# SCH_Genie-V1_2024-08-01.net
KiCad netlist of a schematic drawn in EasyEDA
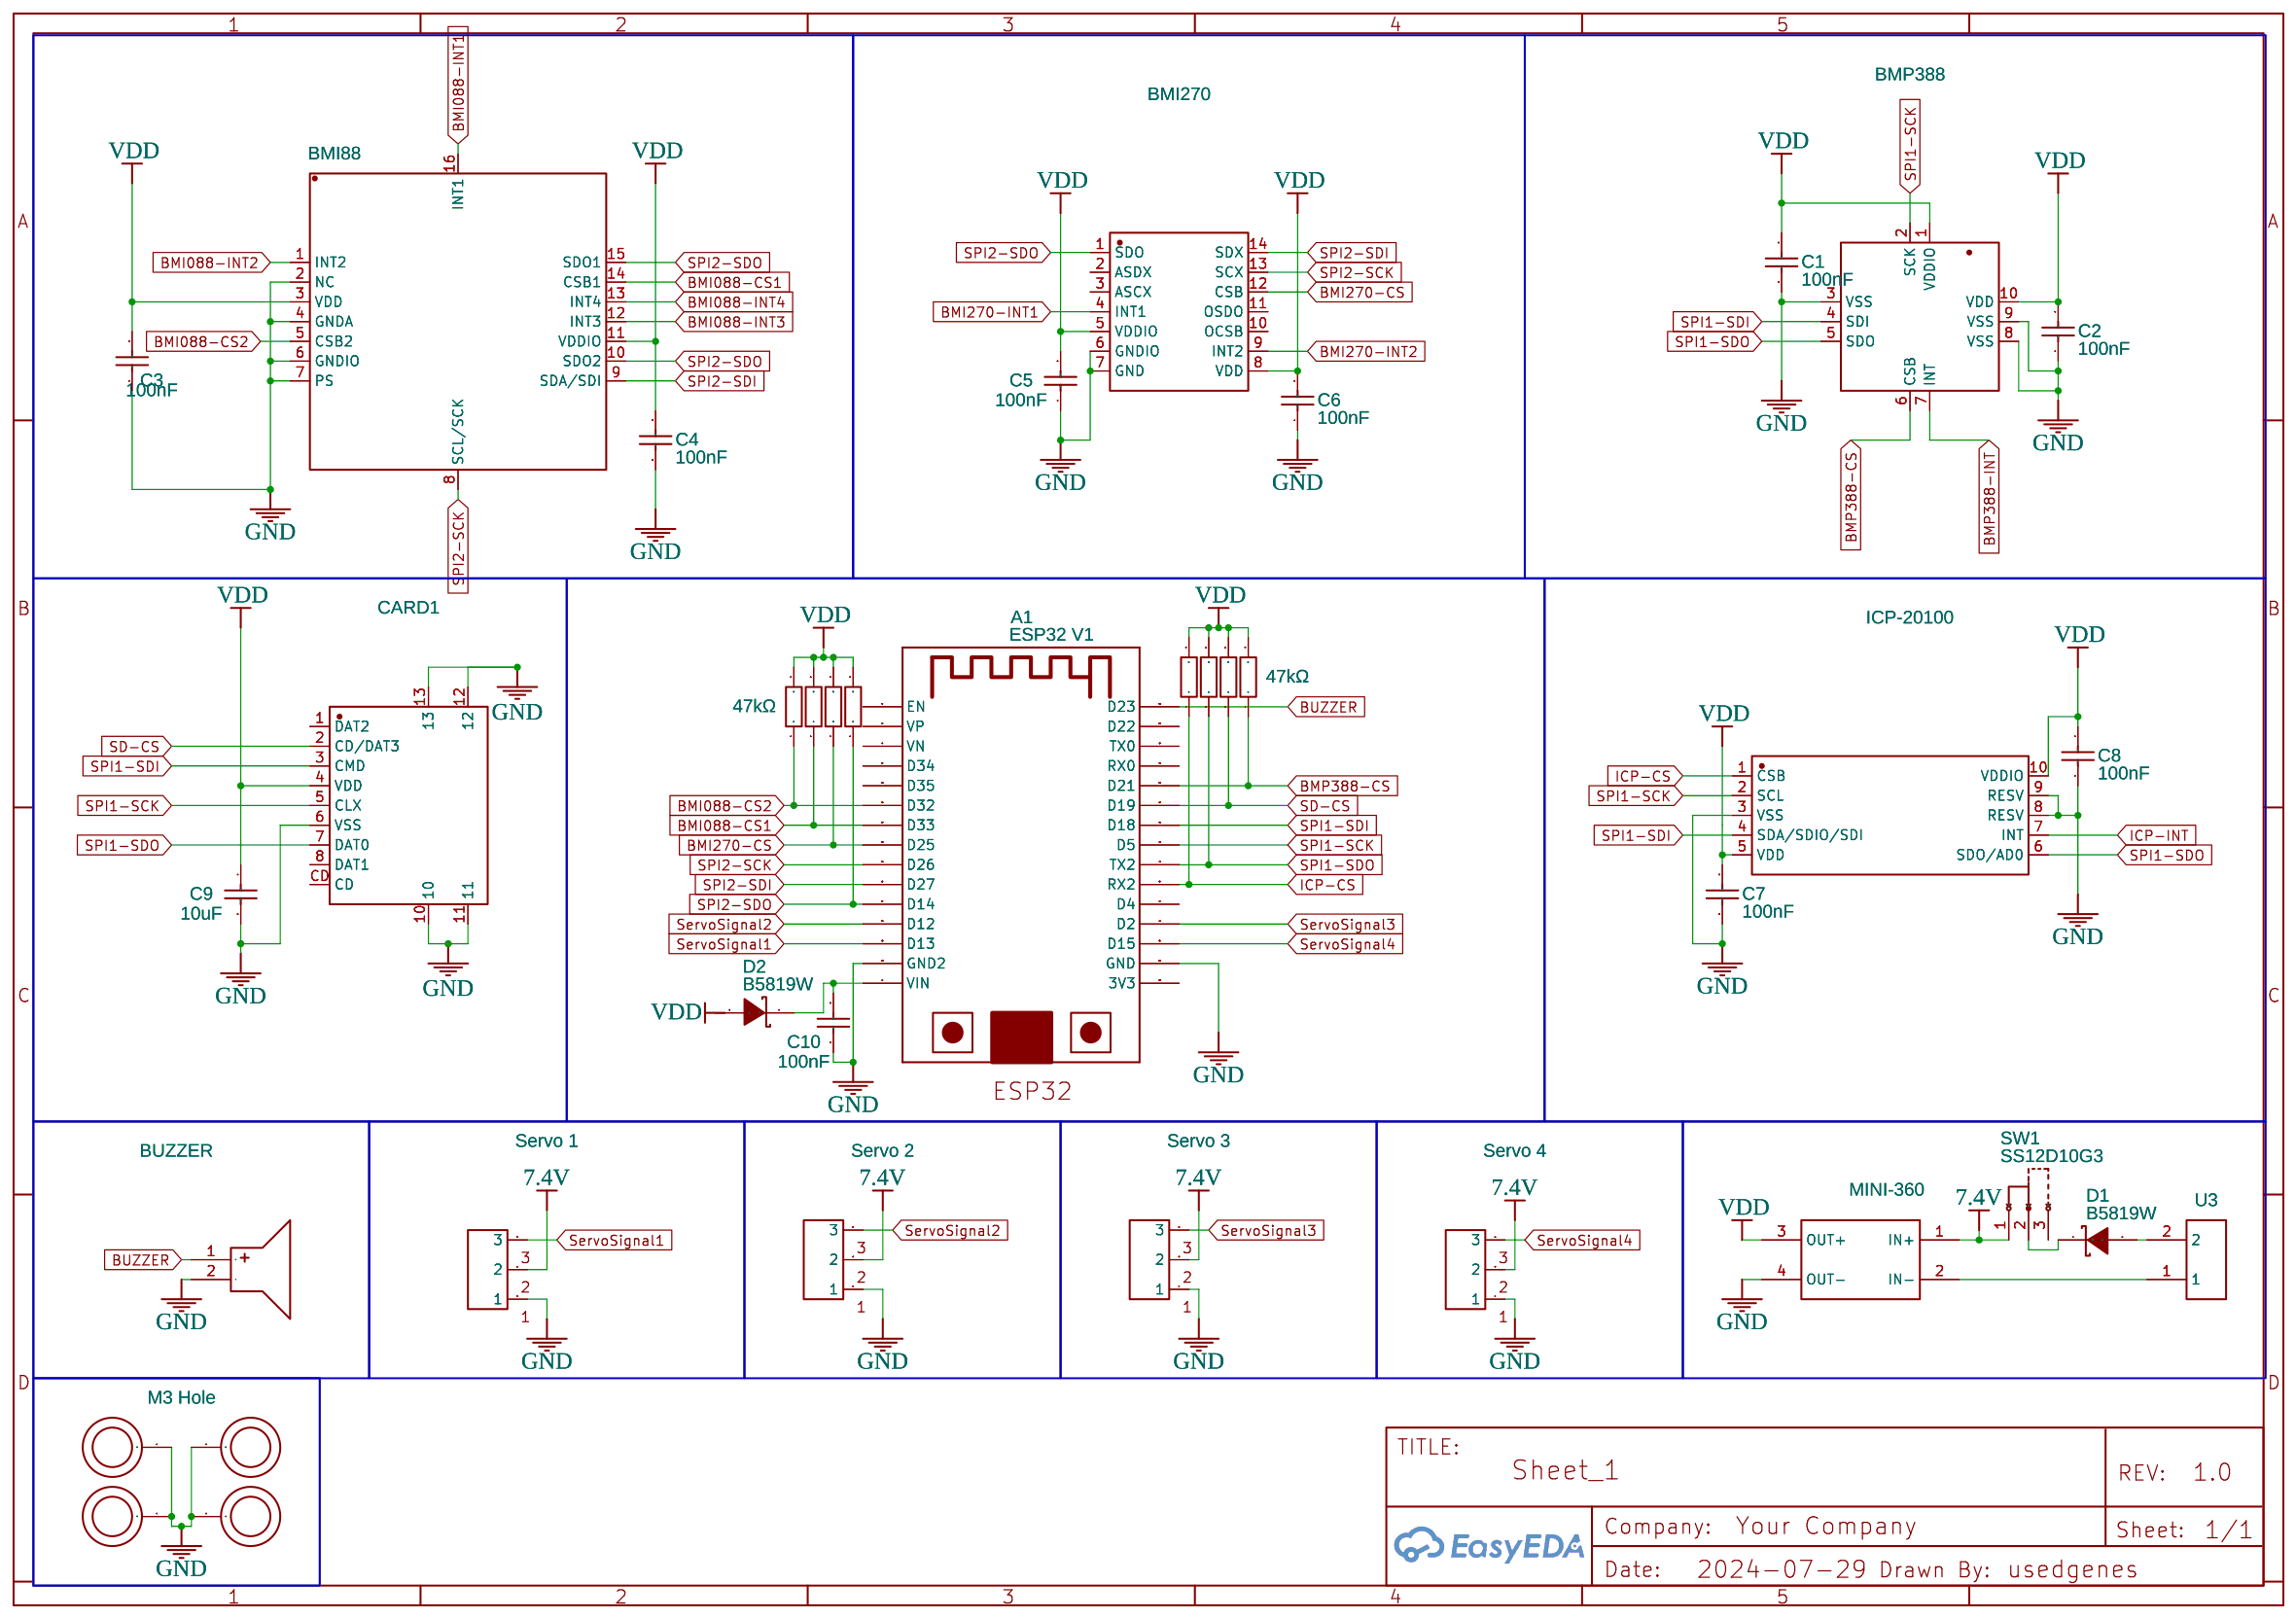
[diagram p0: schematic sheet]

(export (version "E")
  (design (tool "Eeschema 10.0.6"))
  (components
    (comp (ref "A1") (value "ESP32 V1") (libsource (lib "") (part "ESP32-DEVKIT-V1-30PIN")))
    (comp (ref "BMI88")
      (value "BMI088")
      (fields (field (name "Manufacturer") "Bosch(博世)"))
      (libsource (lib "") (part "BMI088"))
    )
    (comp (ref "BMI270")
      (value "BMI270")
      (fields (field (name "Manufacturer") "Bosch(博世)"))
      (libsource (lib "") (part "BMI270"))
    )
    (comp (ref "BMP388")
      (value "BMP388")
      (fields (field (name "Manufacturer") "Bosch(博世)"))
      (libsource (lib "") (part "BMP388"))
    )
    (comp (ref "BUZZER")
      (value "4000Hz")
      (fields
        (field (name "Manufacturer Part") "SKY-1475-0540-45P7.6")
        (field (name "Manufacturer") "S&S(海旭)")
      )
      (libsource (lib "") (part "SKY-1475-0540-45P7.6"))
    )
    (comp (ref "C1")
      (value "100nF")
      (fields
        (field (name "Manufacturer Part") "CL05B104KO5NNNC")
        (field (name "Manufacturer") "SAMSUNG(三星)")
      )
      (libsource (lib "") (part "CL05B104KO5NNNC"))
    )
    (comp (ref "C2")
      (value "100nF")
      (fields
        (field (name "Manufacturer Part") "CL05B104KO5NNNC")
        (field (name "Manufacturer") "SAMSUNG(三星)")
      )
      (libsource (lib "") (part "CL05B104KO5NNNC"))
    )
    (comp (ref "C3")
      (value "100nF")
      (fields
        (field (name "Manufacturer Part") "CL05B104KO5NNNC")
        (field (name "Manufacturer") "SAMSUNG(三星)")
      )
      (libsource (lib "") (part "CL05B104KO5NNNC"))
    )
    (comp (ref "C4")
      (value "100nF")
      (fields
        (field (name "Manufacturer Part") "CL05B104KO5NNNC")
        (field (name "Manufacturer") "SAMSUNG(三星)")
      )
      (libsource (lib "") (part "CL05B104KO5NNNC"))
    )
    (comp (ref "C5")
      (value "100nF")
      (fields
        (field (name "Manufacturer Part") "CL05B104KO5NNNC")
        (field (name "Manufacturer") "SAMSUNG(三星)")
      )
      (libsource (lib "") (part "CL05B104KO5NNNC"))
    )
    (comp (ref "C6")
      (value "100nF")
      (fields
        (field (name "Manufacturer Part") "CL05B104KO5NNNC")
        (field (name "Manufacturer") "SAMSUNG(三星)")
      )
      (libsource (lib "") (part "CL05B104KO5NNNC"))
    )
    (comp (ref "C7")
      (value "100nF")
      (fields
        (field (name "Manufacturer Part") "CL05B104KO5NNNC")
        (field (name "Manufacturer") "SAMSUNG(三星)")
      )
      (libsource (lib "") (part "CL05B104KO5NNNC"))
    )
    (comp (ref "C8")
      (value "100nF")
      (fields
        (field (name "Manufacturer Part") "CL05B104KO5NNNC")
        (field (name "Manufacturer") "SAMSUNG(三星)")
      )
      (libsource (lib "") (part "CL05B104KO5NNNC"))
    )
    (comp (ref "C9")
      (value "10uF")
      (fields
        (field (name "Manufacturer Part") "CL05A106MQ5NUNC")
        (field (name "Manufacturer") "SAMSUNG(三星)")
      )
      (libsource (lib "") (part "CL05A106MQ5NUNC"))
    )
    (comp (ref "C10")
      (value "100nF")
      (fields
        (field (name "Manufacturer Part") "CL05B104KO5NNNC")
        (field (name "Manufacturer") "SAMSUNG(三星)")
      )
      (libsource (lib "") (part "CL05B104KO5NNNC"))
    )
    (comp (ref "CARD1")
      (value "TF PUSH")
      (fields (field (name "Manufacturer") "SHOU HAN(首韩)"))
      (libsource (lib "") (part "TF PUSH"))
    )
    (comp (ref "D1")
      (value "B5819W")
      (fields (field (name "Manufacturer") "MDD(辰达半导体)"))
      (libsource (lib "") (part "B5819W_1"))
    )
    (comp (ref "D2")
      (value "B5819W")
      (fields (field (name "Manufacturer") "MDD(辰达半导体)"))
      (libsource (lib "") (part "B5819W"))
    )
    (comp (ref "H1") (value "M3 Hole") (libsource (lib "") (part "3MM_HOLE_1")))
    (comp (ref "H2") (value "3MM_HOLE") (libsource (lib "") (part "3MM_HOLE")))
    (comp (ref "H3") (value "3MM_HOLE") (libsource (lib "") (part "3MM_HOLE_1")))
    (comp (ref "H4") (value "3MM_HOLE") (libsource (lib "") (part "3MM_HOLE")))
    (comp (ref "ICP-20100")
      (value "ICP-20100")
      (fields (field (name "Manufacturer") "TDK"))
      (libsource (lib "") (part "ICP-20100"))
    )
    (comp (ref "MINI-360") (value "MINI-360") (libsource (lib "") (part "MINI-360")))
    (comp (ref "P1")
      (value "Servo 1")
      (fields
        (field (name "Manufacturer Part") "Female headerHDR1X8-2.54")
        (field (name "Manufacturer") "BOOMELE")
      )
      (libsource (lib "") (part "HEADER PAD 3X RMM COPY"))
    )
    (comp (ref "P2")
      (value "Servo 2")
      (fields
        (field (name "Manufacturer Part") "Female headerHDR1X8-2.54")
        (field (name "Manufacturer") "BOOMELE")
      )
      (libsource (lib "") (part "HEADER PAD 3X RMM COPY"))
    )
    (comp (ref "P3")
      (value "Servo 3")
      (fields
        (field (name "Manufacturer Part") "Female headerHDR1X8-2.54")
        (field (name "Manufacturer") "BOOMELE")
      )
      (libsource (lib "") (part "HEADER PAD 3X RMM COPY"))
    )
    (comp (ref "P4")
      (value "Servo 4")
      (fields
        (field (name "Manufacturer Part") "Female headerHDR1X8-2.54")
        (field (name "Manufacturer") "BOOMELE")
      )
      (libsource (lib "") (part "HEADER PAD 3X RMM COPY"))
    )
    (comp (ref "R1")
      (value "47kΩ")
      (fields
        (field (name "Manufacturer Part") "0402WGF4702TCE")
        (field (name "Manufacturer") "UNI-ROYAL(厚声)")
      )
      (libsource (lib "") (part "0402WGF4702TCE"))
    )
    (comp (ref "R2")
      (value "47kΩ")
      (fields
        (field (name "Manufacturer Part") "0402WGF4702TCE")
        (field (name "Manufacturer") "UNI-ROYAL(厚声)")
      )
      (libsource (lib "") (part "0402WGF4702TCE"))
    )
    (comp (ref "R3")
      (value "47kΩ")
      (fields
        (field (name "Manufacturer Part") "0402WGF4702TCE")
        (field (name "Manufacturer") "UNI-ROYAL(厚声)")
      )
      (libsource (lib "") (part "0402WGF4702TCE"))
    )
    (comp (ref "R4")
      (value "47kΩ")
      (fields
        (field (name "Manufacturer Part") "0402WGF4702TCE")
        (field (name "Manufacturer") "UNI-ROYAL(厚声)")
      )
      (libsource (lib "") (part "0402WGF4702TCE"))
    )
    (comp (ref "R5")
      (value "47kΩ")
      (fields
        (field (name "Manufacturer Part") "0402WGF4702TCE")
        (field (name "Manufacturer") "UNI-ROYAL(厚声)")
      )
      (libsource (lib "") (part "0402WGF4702TCE"))
    )
    (comp (ref "R7")
      (value "47kΩ")
      (fields
        (field (name "Manufacturer Part") "0402WGF4702TCE")
        (field (name "Manufacturer") "UNI-ROYAL(厚声)")
      )
      (libsource (lib "") (part "0402WGF4702TCE"))
    )
    (comp (ref "R8")
      (value "47kΩ")
      (fields
        (field (name "Manufacturer Part") "0402WGF4702TCE")
        (field (name "Manufacturer") "UNI-ROYAL(厚声)")
      )
      (libsource (lib "") (part "0402WGF4702TCE"))
    )
    (comp (ref "R9")
      (value "47kΩ")
      (fields
        (field (name "Manufacturer Part") "0402WGF4702TCE")
        (field (name "Manufacturer") "UNI-ROYAL(厚声)")
      )
      (libsource (lib "") (part "0402WGF4702TCE"))
    )
    (comp (ref "SW1")
      (value "SS12D10G3")
      (fields (field (name "Manufacturer") "SHOU HAN(首韩)"))
      (libsource (lib "") (part "SS12D10G3"))
    )
    (comp (ref "U3") (value "Power Pins") (libsource (lib "") (part "1X2")))
  )
  (nets
    (net (code "1") (name "7.4V") (class "Default")
      (node (ref "MINI-360") (pin "1") (pinfunction "IN+_1") (pintype "unspecified"))
      (node (ref "P1") (pin "2") (pinfunction "2_2") (pintype "unspecified"))
      (node (ref "P2") (pin "2") (pinfunction "2_2") (pintype "unspecified"))
      (node (ref "P3") (pin "2") (pinfunction "2_2") (pintype "unspecified"))
      (node (ref "P4") (pin "2") (pinfunction "2_2") (pintype "unspecified"))
      (node (ref "SW1") (pin "1") (pinfunction "1_1") (pintype "unspecified"))
    )
    (net (code "2") (name "BMI088-CS1") (class "Default")
      (node (ref "A1") (pin "D33") (pinfunction "D33_D33") (pintype "unspecified"))
      (node (ref "BMI88") (pin "14") (pinfunction "CSB1_14") (pintype "unspecified"))
      (node (ref "R1") (pin "1") (pinfunction "1_1") (pintype "input"))
    )
    (net (code "3") (name "BMI088-CS2") (class "Default")
      (node (ref "A1") (pin "D32") (pinfunction "D32_D32") (pintype "unspecified"))
      (node (ref "BMI88") (pin "5") (pinfunction "CSB2_5") (pintype "unspecified"))
      (node (ref "R4") (pin "1") (pinfunction "1_1") (pintype "input"))
    )
    (net (code "4") (name "BMI088-INT1") (class "Default")
      (node (ref "BMI88") (pin "16") (pinfunction "INT1_16") (pintype "unspecified"))
    )
    (net (code "5") (name "BMI088-INT2") (class "Default")
      (node (ref "BMI88") (pin "1") (pinfunction "INT2_1") (pintype "unspecified"))
    )
    (net (code "6") (name "BMI088-INT3") (class "Default")
      (node (ref "BMI88") (pin "12") (pinfunction "INT3_12") (pintype "unspecified"))
    )
    (net (code "7") (name "BMI088-INT4") (class "Default")
      (node (ref "BMI88") (pin "13") (pinfunction "INT4_13") (pintype "unspecified"))
    )
    (net (code "8") (name "BMI270-CS") (class "Default")
      (node (ref "A1") (pin "D25") (pinfunction "D25_D25") (pintype "unspecified"))
      (node (ref "BMI270") (pin "12") (pinfunction "CSB_12") (pintype "unspecified"))
      (node (ref "R2") (pin "1") (pinfunction "1_1") (pintype "input"))
    )
    (net (code "9") (name "BMI270-INT1") (class "Default")
      (node (ref "BMI270") (pin "4") (pinfunction "INT1_4") (pintype "unspecified"))
    )
    (net (code "10") (name "BMI270-INT2") (class "Default")
      (node (ref "BMI270") (pin "9") (pinfunction "INT2_9") (pintype "unspecified"))
    )
    (net (code "11") (name "BMP388-CS") (class "Default")
      (node (ref "A1") (pin "D21") (pinfunction "D21_D21") (pintype "unspecified"))
      (node (ref "BMP388") (pin "6") (pinfunction "CSB_6") (pintype "unspecified"))
      (node (ref "R5") (pin "1") (pinfunction "1_1") (pintype "input"))
    )
    (net (code "12") (name "BMP388-INT") (class "Default")
      (node (ref "BMP388") (pin "7") (pinfunction "INT_7") (pintype "unspecified"))
    )
    (net (code "13") (name "BUZZER") (class "Default")
      (node (ref "A1") (pin "D23") (pinfunction "D23_D23") (pintype "unspecified"))
      (node (ref "BUZZER") (pin "1") (pinfunction "+_1") (pintype "unspecified"))
    )
    (net (code "14") (name "GND") (class "Default")
      (node (ref "A1") (pin "GND") (pinfunction "GND_GND") (pintype "unspecified"))
      (node (ref "A1") (pin "GND2") (pinfunction "GND2_GND2") (pintype "unspecified"))
      (node (ref "BMI270") (pin "6") (pinfunction "GNDIO_6") (pintype "unspecified"))
      (node (ref "BMI270") (pin "7") (pinfunction "GND_7") (pintype "unspecified"))
      (node (ref "BMI88") (pin "2") (pinfunction "NC_2") (pintype "unspecified"))
      (node (ref "BMI88") (pin "4") (pinfunction "GNDA_4") (pintype "unspecified"))
      (node (ref "BMI88") (pin "6") (pinfunction "GNDIO_6") (pintype "unspecified"))
      (node (ref "BMI88") (pin "7") (pinfunction "PS_7") (pintype "unspecified"))
      (node (ref "BMP388") (pin "3") (pinfunction "VSS_3") (pintype "unspecified"))
      (node (ref "BMP388") (pin "8") (pinfunction "VSS_8") (pintype "unspecified"))
      (node (ref "BMP388") (pin "9") (pinfunction "VSS_9") (pintype "unspecified"))
      (node (ref "BUZZER") (pin "2") (pinfunction "-_2") (pintype "unspecified"))
      (node (ref "C1") (pin "1") (pinfunction "1_1") (pintype "input"))
      (node (ref "C10") (pin "1") (pinfunction "1_1") (pintype "input"))
      (node (ref "C2") (pin "1") (pinfunction "1_1") (pintype "input"))
      (node (ref "C3") (pin "1") (pinfunction "1_1") (pintype "input"))
      (node (ref "C4") (pin "1") (pinfunction "1_1") (pintype "input"))
      (node (ref "C5") (pin "1") (pinfunction "1_1") (pintype "input"))
      (node (ref "C6") (pin "1") (pinfunction "1_1") (pintype "input"))
      (node (ref "C7") (pin "1") (pinfunction "1_1") (pintype "input"))
      (node (ref "C8") (pin "1") (pinfunction "1_1") (pintype "input"))
      (node (ref "C9") (pin "2") (pinfunction "2_2") (pintype "input"))
      (node (ref "CARD1") (pin "10") (pinfunction "10_10") (pintype "unspecified"))
      (node (ref "CARD1") (pin "11") (pinfunction "11_11") (pintype "unspecified"))
      (node (ref "CARD1") (pin "12") (pinfunction "12_12") (pintype "unspecified"))
      (node (ref "CARD1") (pin "13") (pinfunction "13_13") (pintype "unspecified"))
      (node (ref "CARD1") (pin "6") (pinfunction "VSS_6") (pintype "unspecified"))
      (node (ref "H1") (pin "1") (pinfunction "1_1") (pintype "bidirectional"))
      (node (ref "H2") (pin "1") (pinfunction "1_1") (pintype "bidirectional"))
      (node (ref "H3") (pin "1") (pinfunction "1_1") (pintype "bidirectional"))
      (node (ref "H4") (pin "1") (pinfunction "1_1") (pintype "bidirectional"))
      (node (ref "ICP-20100") (pin "3") (pinfunction "VSS_3") (pintype "unspecified"))
      (node (ref "ICP-20100") (pin "8") (pinfunction "RESV_8") (pintype "unspecified"))
      (node (ref "ICP-20100") (pin "9") (pinfunction "RESV_9") (pintype "unspecified"))
      (node (ref "MINI-360") (pin "4") (pinfunction "OUT-_4") (pintype "unspecified"))
      (node (ref "P1") (pin "1") (pinfunction "1_1") (pintype "unspecified"))
      (node (ref "P2") (pin "1") (pinfunction "1_1") (pintype "unspecified"))
      (node (ref "P3") (pin "1") (pinfunction "1_1") (pintype "unspecified"))
      (node (ref "P4") (pin "1") (pinfunction "1_1") (pintype "unspecified"))
    )
    (net (code "15") (name "ICP-CS") (class "Default")
      (node (ref "A1") (pin "RX2") (pinfunction "RX2_RX2") (pintype "unspecified"))
      (node (ref "ICP-20100") (pin "1") (pinfunction "CSB_1") (pintype "unspecified"))
      (node (ref "R8") (pin "1") (pinfunction "1_1") (pintype "input"))
    )
    (net (code "16") (name "ICP-INT") (class "Default")
      (node (ref "ICP-20100") (pin "7") (pinfunction "INT_7") (pintype "unspecified"))
    )
    (net (code "17") (name "Net-(D1-A)") (class "Default")
      (node (ref "D1") (pin "2") (pinfunction "A_2") (pintype "unspecified"))
      (node (ref "U3") (pin "2") (pinfunction "2_2") (pintype "unspecified"))
    )
    (net (code "18") (name "Net-(D1-K)") (class "Default")
      (node (ref "D1") (pin "1") (pinfunction "K_1") (pintype "unspecified"))
      (node (ref "SW1") (pin "2") (pinfunction "2_2") (pintype "unspecified"))
    )
    (net (code "19") (name "Net-(D2-K)") (class "Default")
      (node (ref "A1") (pin "VIN") (pinfunction "VIN_VIN") (pintype "unspecified"))
      (node (ref "C10") (pin "2") (pinfunction "2_2") (pintype "input"))
      (node (ref "D2") (pin "1") (pinfunction "K_1") (pintype "unspecified"))
    )
    (net (code "20") (name "Net-(MINI-360-IN-)") (class "Default")
      (node (ref "MINI-360") (pin "2") (pinfunction "IN-_2") (pintype "unspecified"))
      (node (ref "U3") (pin "1") (pinfunction "1_1") (pintype "unspecified"))
    )
    (net (code "21") (name "SD-CS") (class "Default")
      (node (ref "A1") (pin "D19") (pinfunction "D19_D19") (pintype "unspecified"))
      (node (ref "CARD1") (pin "2") (pinfunction "CD/DAT3_2") (pintype "unspecified"))
      (node (ref "R7") (pin "1") (pinfunction "1_1") (pintype "input"))
    )
    (net (code "22") (name "SPI1-SCK") (class "Default")
      (node (ref "A1") (pin "D5") (pinfunction "D5_D5") (pintype "unspecified"))
      (node (ref "BMP388") (pin "2") (pinfunction "SCK_2") (pintype "unspecified"))
      (node (ref "CARD1") (pin "5") (pinfunction "CLX_5") (pintype "unspecified"))
      (node (ref "ICP-20100") (pin "2") (pinfunction "SCL_2") (pintype "unspecified"))
    )
    (net (code "23") (name "SPI1-SDI") (class "Default")
      (node (ref "A1") (pin "D18") (pinfunction "D18_D18") (pintype "unspecified"))
      (node (ref "BMP388") (pin "4") (pinfunction "SDI_4") (pintype "unspecified"))
      (node (ref "CARD1") (pin "3") (pinfunction "CMD_3") (pintype "unspecified"))
      (node (ref "ICP-20100") (pin "4") (pinfunction "SDA/SDIO/SDI_4") (pintype "unspecified"))
    )
    (net (code "24") (name "SPI1-SDO") (class "Default")
      (node (ref "A1") (pin "TX2") (pinfunction "TX2_TX2") (pintype "unspecified"))
      (node (ref "BMP388") (pin "5") (pinfunction "SDO_5") (pintype "unspecified"))
      (node (ref "CARD1") (pin "7") (pinfunction "DAT0_7") (pintype "unspecified"))
      (node (ref "ICP-20100") (pin "6") (pinfunction "SDO/AD0_6") (pintype "unspecified"))
      (node (ref "R9") (pin "1") (pinfunction "1_1") (pintype "input"))
    )
    (net (code "25") (name "SPI2-SCK") (class "Default")
      (node (ref "A1") (pin "D26") (pinfunction "D26_D26") (pintype "unspecified"))
      (node (ref "BMI270") (pin "13") (pinfunction "SCX_13") (pintype "unspecified"))
      (node (ref "BMI88") (pin "8") (pinfunction "SCL/SCK_8") (pintype "unspecified"))
    )
    (net (code "26") (name "SPI2-SDI") (class "Default")
      (node (ref "A1") (pin "D27") (pinfunction "D27_D27") (pintype "unspecified"))
      (node (ref "BMI270") (pin "14") (pinfunction "SDX_14") (pintype "unspecified"))
      (node (ref "BMI88") (pin "9") (pinfunction "SDA/SDI_9") (pintype "unspecified"))
    )
    (net (code "27") (name "SPI2-SDO") (class "Default")
      (node (ref "A1") (pin "D14") (pinfunction "D14_D14") (pintype "unspecified"))
      (node (ref "BMI270") (pin "1") (pinfunction "SDO_1") (pintype "unspecified"))
      (node (ref "BMI88") (pin "10") (pinfunction "SDO2_10") (pintype "unspecified"))
      (node (ref "BMI88") (pin "15") (pinfunction "SDO1_15") (pintype "unspecified"))
      (node (ref "R3") (pin "1") (pinfunction "1_1") (pintype "input"))
    )
    (net (code "28") (name "ServoSignal1") (class "Default")
      (node (ref "A1") (pin "D13") (pinfunction "D13_D13") (pintype "unspecified"))
      (node (ref "P1") (pin "3") (pinfunction "3_3") (pintype "unspecified"))
    )
    (net (code "29") (name "ServoSignal2") (class "Default")
      (node (ref "A1") (pin "D12") (pinfunction "D12_D12") (pintype "unspecified"))
      (node (ref "P2") (pin "3") (pinfunction "3_3") (pintype "unspecified"))
    )
    (net (code "30") (name "ServoSignal3") (class "Default")
      (node (ref "A1") (pin "D2") (pinfunction "D2_D2") (pintype "unspecified"))
      (node (ref "P3") (pin "3") (pinfunction "3_3") (pintype "unspecified"))
    )
    (net (code "31") (name "ServoSignal4") (class "Default")
      (node (ref "A1") (pin "D15") (pinfunction "D15_D15") (pintype "unspecified"))
      (node (ref "P4") (pin "3") (pinfunction "3_3") (pintype "unspecified"))
    )
    (net (code "32") (name "VDD") (class "Default")
      (node (ref "BMI270") (pin "5") (pinfunction "VDDIO_5") (pintype "unspecified"))
      (node (ref "BMI270") (pin "8") (pinfunction "VDD_8") (pintype "unspecified"))
      (node (ref "BMI88") (pin "11") (pinfunction "VDDIO_11") (pintype "unspecified"))
      (node (ref "BMI88") (pin "3") (pinfunction "VDD_3") (pintype "unspecified"))
      (node (ref "BMP388") (pin "1") (pinfunction "VDDIO_1") (pintype "unspecified"))
      (node (ref "BMP388") (pin "10") (pinfunction "VDD_10") (pintype "unspecified"))
      (node (ref "C1") (pin "2") (pinfunction "2_2") (pintype "input"))
      (node (ref "C2") (pin "2") (pinfunction "2_2") (pintype "input"))
      (node (ref "C3") (pin "2") (pinfunction "2_2") (pintype "input"))
      (node (ref "C4") (pin "2") (pinfunction "2_2") (pintype "input"))
      (node (ref "C5") (pin "2") (pinfunction "2_2") (pintype "input"))
      (node (ref "C6") (pin "2") (pinfunction "2_2") (pintype "input"))
      (node (ref "C7") (pin "2") (pinfunction "2_2") (pintype "input"))
      (node (ref "C8") (pin "2") (pinfunction "2_2") (pintype "input"))
      (node (ref "C9") (pin "1") (pinfunction "1_1") (pintype "input"))
      (node (ref "CARD1") (pin "4") (pinfunction "VDD_4") (pintype "unspecified"))
      (node (ref "D2") (pin "2") (pinfunction "A_2") (pintype "unspecified"))
      (node (ref "ICP-20100") (pin "10") (pinfunction "VDDIO_10") (pintype "unspecified"))
      (node (ref "ICP-20100") (pin "5") (pinfunction "VDD_5") (pintype "unspecified"))
      (node (ref "MINI-360") (pin "3") (pinfunction "OUT+_3") (pintype "unspecified"))
      (node (ref "R1") (pin "2") (pinfunction "2_2") (pintype "input"))
      (node (ref "R2") (pin "2") (pinfunction "2_2") (pintype "input"))
      (node (ref "R3") (pin "2") (pinfunction "2_2") (pintype "input"))
      (node (ref "R4") (pin "2") (pinfunction "2_2") (pintype "input"))
      (node (ref "R5") (pin "2") (pinfunction "2_2") (pintype "input"))
      (node (ref "R7") (pin "2") (pinfunction "2_2") (pintype "input"))
      (node (ref "R8") (pin "2") (pinfunction "2_2") (pintype "input"))
      (node (ref "R9") (pin "2") (pinfunction "2_2") (pintype "input"))
    )
    (net (code "33") (name "unconnected-(A1-Pad3V3)") (class "Default")
      (node (ref "A1") (pin "3V3") (pinfunction "3V3_3V3") (pintype "unspecified"))
    )
    (net (code "34") (name "unconnected-(A1-PadD4)") (class "Default")
      (node (ref "A1") (pin "D4") (pinfunction "D4_D4") (pintype "unspecified"))
    )
    (net (code "35") (name "unconnected-(A1-PadD22)") (class "Default")
      (node (ref "A1") (pin "D22") (pinfunction "D22_D22") (pintype "unspecified"))
    )
    (net (code "36") (name "unconnected-(A1-PadD34)") (class "Default")
      (node (ref "A1") (pin "D34") (pinfunction "D34_D34") (pintype "unspecified"))
    )
    (net (code "37") (name "unconnected-(A1-PadD35)") (class "Default")
      (node (ref "A1") (pin "D35") (pinfunction "D35_D35") (pintype "unspecified"))
    )
    (net (code "38") (name "unconnected-(A1-PadEN)") (class "Default")
      (node (ref "A1") (pin "EN") (pinfunction "EN_EN") (pintype "unspecified"))
    )
    (net (code "39") (name "unconnected-(A1-PadRX0)") (class "Default")
      (node (ref "A1") (pin "RX0") (pinfunction "RX0_RX0") (pintype "unspecified"))
    )
    (net (code "40") (name "unconnected-(A1-PadTX0)") (class "Default")
      (node (ref "A1") (pin "TX0") (pinfunction "TX0_TX0") (pintype "unspecified"))
    )
    (net (code "41") (name "unconnected-(A1-PadVN)") (class "Default")
      (node (ref "A1") (pin "VN") (pinfunction "VN_VN") (pintype "unspecified"))
    )
    (net (code "42") (name "unconnected-(A1-PadVP)") (class "Default")
      (node (ref "A1") (pin "VP") (pinfunction "VP_VP") (pintype "unspecified"))
    )
    (net (code "43") (name "unconnected-(BMI270-ASCX-Pad3)") (class "Default")
      (node (ref "BMI270") (pin "3") (pinfunction "ASCX_3") (pintype "unspecified"))
    )
    (net (code "44") (name "unconnected-(BMI270-ASDX-Pad2)") (class "Default")
      (node (ref "BMI270") (pin "2") (pinfunction "ASDX_2") (pintype "unspecified"))
    )
    (net (code "45") (name "unconnected-(BMI270-OCSB-Pad10)") (class "Default")
      (node (ref "BMI270") (pin "10") (pinfunction "OCSB_10") (pintype "unspecified"))
    )
    (net (code "46") (name "unconnected-(BMI270-OSDO-Pad11)") (class "Default")
      (node (ref "BMI270") (pin "11") (pinfunction "OSDO_11") (pintype "unspecified"))
    )
    (net (code "47") (name "unconnected-(CARD1-DAT1-Pad8)") (class "Default")
      (node (ref "CARD1") (pin "8") (pinfunction "DAT1_8") (pintype "unspecified"))
    )
    (net (code "48") (name "unconnected-(CARD1-DAT2-Pad1)") (class "Default")
      (node (ref "CARD1") (pin "1") (pinfunction "DAT2_1") (pintype "unspecified"))
    )
    (net (code "49") (name "unconnected-(CARD1-PadCD)") (class "Default")
      (node (ref "CARD1") (pin "CD") (pinfunction "CD_CD") (pintype "unspecified"))
    )
    (net (code "50") (name "unconnected-(SW1-Pad3)") (class "Default")
      (node (ref "SW1") (pin "3") (pinfunction "3_3") (pintype "unspecified"))
    )
  )
)
